# DAC_AMP.net
KiCad netlist of a schematic drawn in Altium Designer
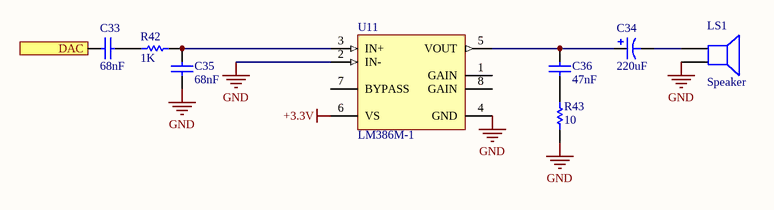
[diagram p0: DAC AMP.SchDoc]

(export (version "E")
  (design (tool "Eeschema 10.0.6"))
  (components
    (comp (ref "C33")
      (value "68nF")
      (footprint "C603")
      (description "Capacitor")
      (fields (field (name "DESIGNER") "Parsa Malekpour"))
      (libsource (lib "UserPKG") (part "Cap"))
    )
    (comp (ref "C34")
      (value "220uF")
      (footprint "CAP-TAN-A")
      (description "Polar Capacitor")
      (fields (field (name "VOLTAGE") "10V"))
      (libsource (lib "UserPKG") (part "CAP-POL"))
    )
    (comp (ref "C35")
      (value "68nF")
      (footprint "C603")
      (description "Capacitor")
      (fields (field (name "DESIGNER") "Parsa Malekpour"))
      (libsource (lib "UserPKG") (part "Cap"))
    )
    (comp (ref "C36")
      (value "47nF")
      (footprint "C603")
      (description "Capacitor")
      (fields (field (name "DESIGNER") "Parsa Malekpour"))
      (libsource (lib "UserPKG") (part "Cap"))
    )
    (comp (ref "LS1")
      (value "Speaker")
      (footprint "ph-2")
      (description "Loudspeaker")
      (fields (field (name "PUBLISHER") "Altium Limited"))
      (libsource (lib "Miscellaneous Devices") (part "Speaker"))
    )
    (comp (ref "R42")
      (value "1K")
      (footprint "R0603")
      (description "Resistor")
      (fields (field (name "DESIGNER") "Parsa Malekpour"))
      (libsource (lib "UserPKG") (part "Resistor"))
    )
    (comp (ref "R43")
      (value "10")
      (footprint "R0603")
      (description "Resistor")
      (fields (field (name "DESIGNER") "Parsa Malekpour"))
      (libsource (lib "UserPKG") (part "Resistor"))
    )
    (comp (ref "U11")
      (value "LM386M-1")
      (footprint "SOIC-8N")
      (description "Low Voltage Audio Power Amplifier, 8-pin Narrow SOIC")
      (fields (field (name "MANUFACTURER") "National Semiconductor"))
      (libsource (lib "National Semiconductor Audio") (part "LM386M-1"))
    )
  )
  (nets
    (net (code "1") (name "+3.3V") (class "Default")
      (node (ref "U11") (pin "6") (pinfunction "VS_6") (pintype "power_in"))
    )
    (net (code "2") (name "/DAC") (class "Default")
      (node (ref "C33") (pin "1") (pinfunction "1_1") (pintype "passive"))
    )
    (net (code "3") (name "GND") (class "Default")
      (node (ref "C35") (pin "1") (pinfunction "1_1") (pintype "passive"))
      (node (ref "LS1") (pin "2") (pinfunction "2_2") (pintype "passive"))
      (node (ref "R43") (pin "1") (pinfunction "1_1") (pintype "passive"))
      (node (ref "U11") (pin "2") (pinfunction "IN-_2") (pintype "input"))
      (node (ref "U11") (pin "4") (pinfunction "GND_4") (pintype "power_in"))
    )
    (net (code "4") (name "Net-(C33-Pad2)") (class "Default")
      (node (ref "C33") (pin "2") (pinfunction "2_2") (pintype "passive"))
      (node (ref "R42") (pin "1") (pinfunction "1_1") (pintype "passive"))
    )
    (net (code "5") (name "Net-(C34-Pad2)") (class "Default")
      (node (ref "C34") (pin "2") (pinfunction "2_2") (pintype "passive"))
      (node (ref "LS1") (pin "1") (pinfunction "1_1") (pintype "passive"))
    )
    (net (code "6") (name "Net-(C36-Pad1)") (class "Default")
      (node (ref "C36") (pin "1") (pinfunction "1_1") (pintype "passive"))
      (node (ref "R43") (pin "2") (pinfunction "2_2") (pintype "passive"))
    )
    (net (code "7") (name "Net-(U11-IN+)") (class "Default")
      (node (ref "C35") (pin "2") (pinfunction "2_2") (pintype "passive"))
      (node (ref "R42") (pin "2") (pinfunction "2_2") (pintype "passive"))
      (node (ref "U11") (pin "3") (pinfunction "IN+_3") (pintype "input"))
    )
    (net (code "8") (name "Net-(U11-VOUT)") (class "Default")
      (node (ref "C34") (pin "1") (pinfunction "1_1") (pintype "passive"))
      (node (ref "C36") (pin "2") (pinfunction "2_2") (pintype "passive"))
      (node (ref "U11") (pin "5") (pinfunction "VOUT_5") (pintype "output"))
    )
    (net (code "9") (name "unconnected-(U11-BYPASS-Pad7)") (class "Default")
      (node (ref "U11") (pin "7") (pinfunction "BYPASS_7") (pintype "passive"))
    )
    (net (code "10") (name "unconnected-(U11-GAIN-Pad1)") (class "Default")
      (node (ref "U11") (pin "1") (pinfunction "GAIN_1") (pintype "passive"))
    )
    (net (code "11") (name "unconnected-(U11-GAIN-Pad8)") (class "Default")
      (node (ref "U11") (pin "8") (pinfunction "GAIN_8") (pintype "passive"))
    )
  )
)
